# greenhousectrl-lab.net
KiCad netlist of a schematic drawn in EAGLE
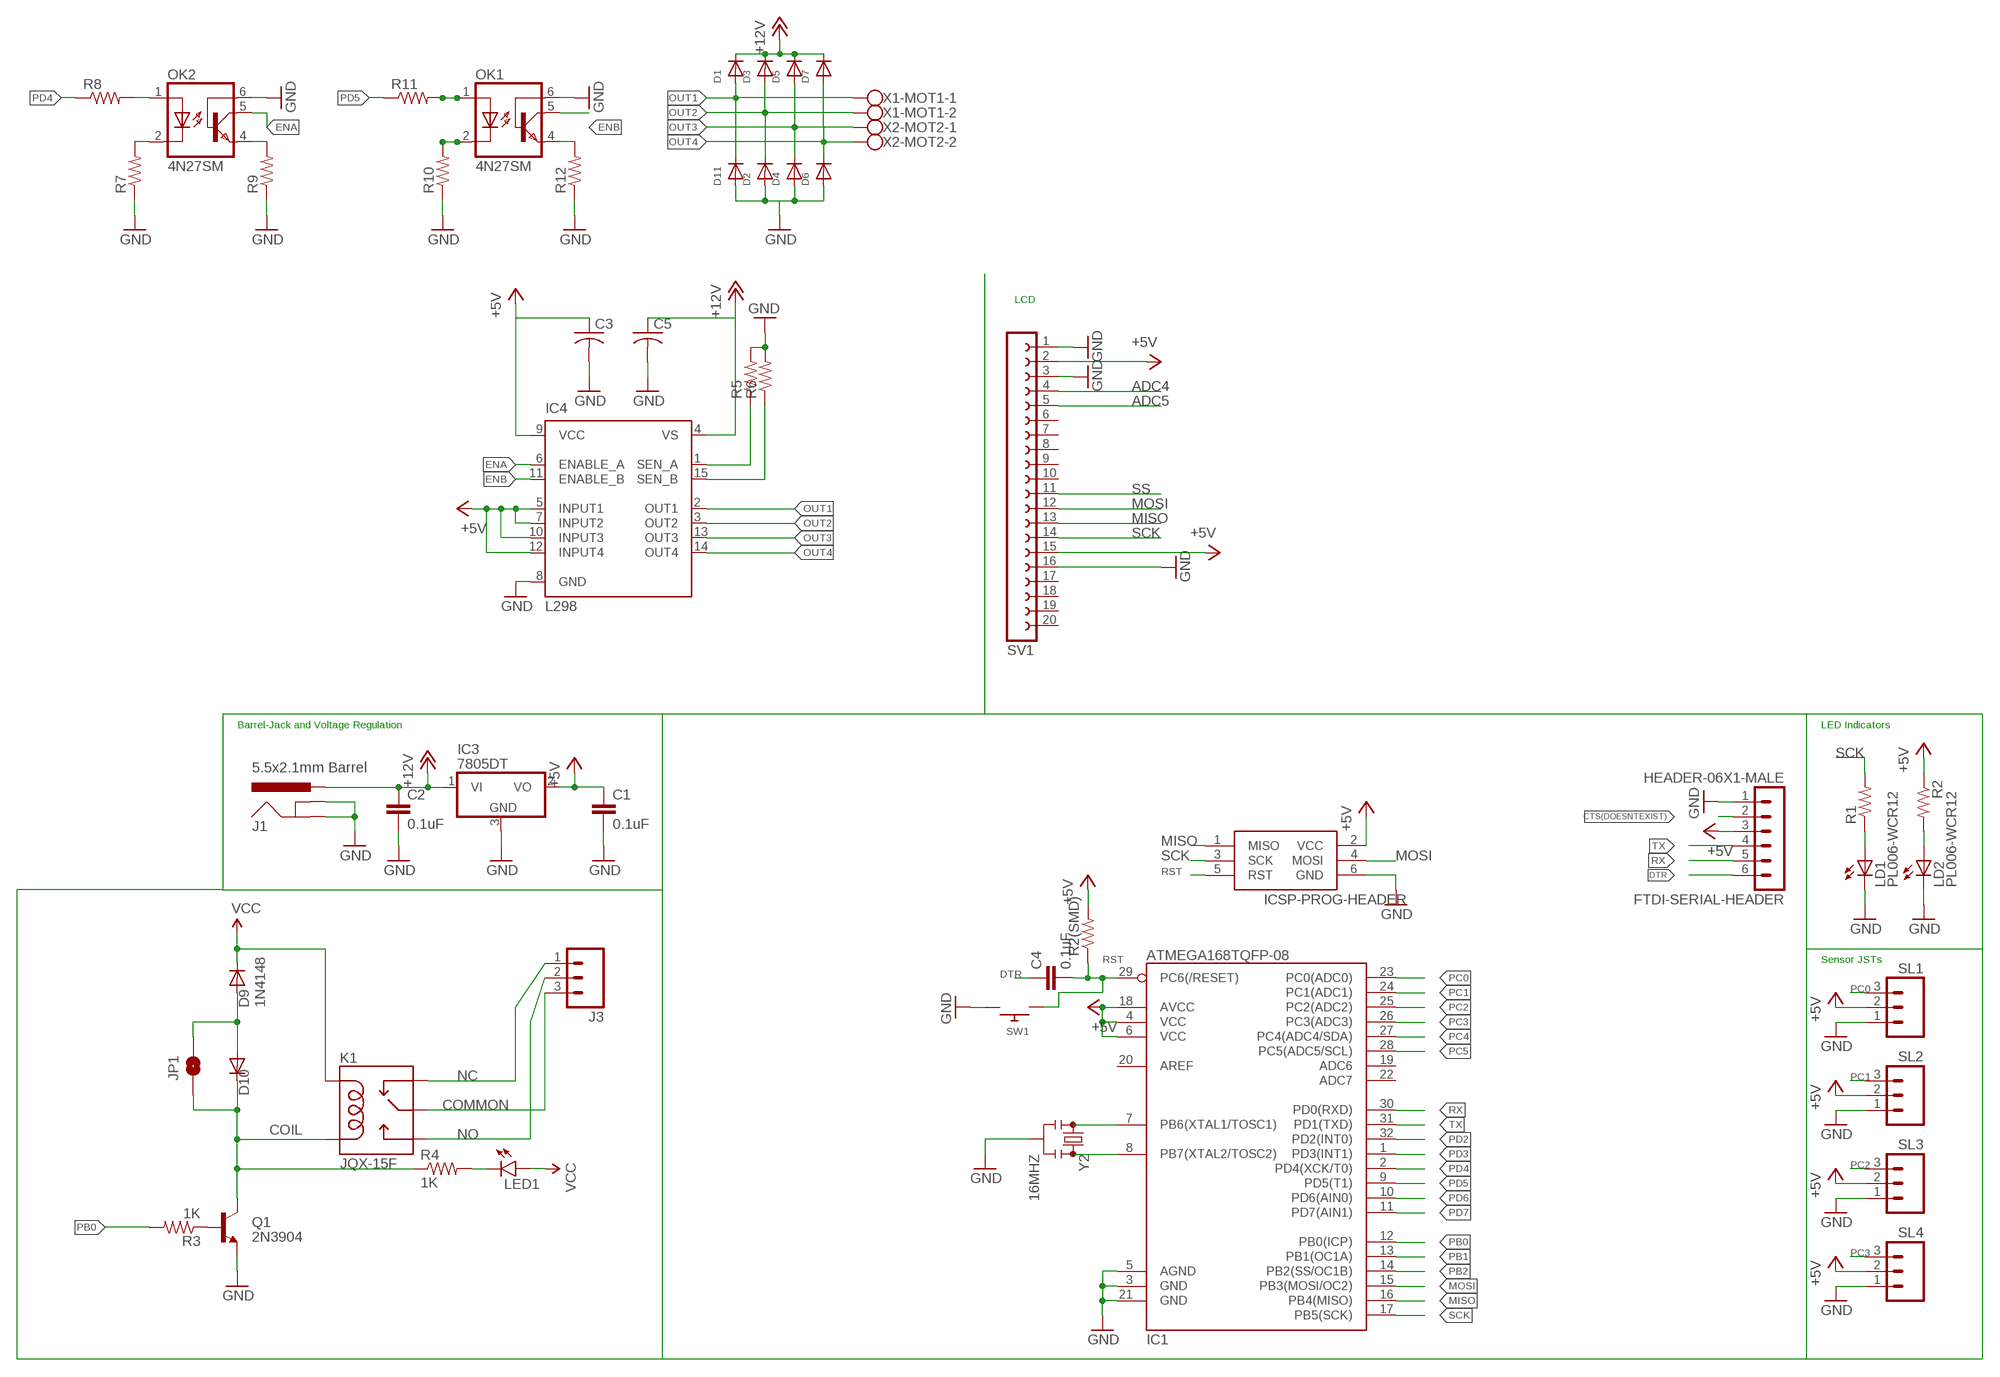
[diagram p0: schematic, sheet 1]

(export (version "E")
  (design (tool "Eeschema 10.0.6"))
  (components
    (comp (ref "C1")
      (value "0.1uF")
      (footprint "eagle-import:0603-CAP")
      (libsource (lib "eagle-import") (part "0.1UF-25V(+80/-20%)(0603)"))
    )
    (comp (ref "C2")
      (value "0.1uF")
      (footprint "eagle-import:0603-CAP")
      (libsource (lib "eagle-import") (part "0.1UF-25V(+80/-20%)(0603)"))
    )
    (comp (ref "C3")
      (value "C-US025-024X044")
      (footprint "eagle-import:C025-024X044")
      (libsource (lib "eagle-import") (part "C-US025-024X044"))
    )
    (comp (ref "C4")
      (value "0.1uF")
      (footprint "eagle-import:0603-CAP")
      (libsource (lib "eagle-import") (part "0.1UF-25V(+80/-20%)(0603)"))
    )
    (comp (ref "C5")
      (value "C-US025-024X044")
      (footprint "eagle-import:C025-024X044")
      (libsource (lib "eagle-import") (part "C-US025-024X044"))
    )
    (comp (ref "D1")
      (value "DIODESMA")
      (footprint "eagle-import:SMADIODE")
      (libsource (lib "eagle-import") (part "DIODESMA"))
    )
    (comp (ref "D2")
      (value "DIODESMA")
      (footprint "eagle-import:SMADIODE")
      (libsource (lib "eagle-import") (part "DIODESMA"))
    )
    (comp (ref "D3")
      (value "DIODESMA")
      (footprint "eagle-import:SMADIODE")
      (libsource (lib "eagle-import") (part "DIODESMA"))
    )
    (comp (ref "D4")
      (value "DIODESMA")
      (footprint "eagle-import:SMADIODE")
      (libsource (lib "eagle-import") (part "DIODESMA"))
    )
    (comp (ref "D5")
      (value "DIODESMA")
      (footprint "eagle-import:SMADIODE")
      (libsource (lib "eagle-import") (part "DIODESMA"))
    )
    (comp (ref "D6")
      (value "DIODESMA")
      (footprint "eagle-import:SMADIODE")
      (libsource (lib "eagle-import") (part "DIODESMA"))
    )
    (comp (ref "D7")
      (value "DIODESMA")
      (footprint "eagle-import:SMADIODE")
      (libsource (lib "eagle-import") (part "DIODESMA"))
    )
    (comp (ref "D9")
      (value "1N4148")
      (footprint "eagle-import:SOD-323F")
      (libsource (lib "eagle-import") (part "DIODESOD-323F"))
    )
    (comp (ref "D10")
      (value "Zener")
      (footprint "eagle-import:SOD-323F")
      (libsource (lib "eagle-import") (part "DIODESOD-323F"))
    )
    (comp (ref "D11")
      (value "DIODESMA")
      (footprint "eagle-import:SMADIODE")
      (libsource (lib "eagle-import") (part "DIODESMA"))
    )
    (comp (ref "FTDI-SERIAL-HEADER")
      (value "HEADER-06X1-MALE")
      (footprint "eagle-import:06X1-PTH")
      (libsource (lib "eagle-import") (part "HEADER-06X1?-MALE"))
    )
    (comp (ref "IC1")
      (value "ATMEGA168TQFP-08")
      (footprint "eagle-import:TQFP32-08")
      (libsource (lib "eagle-import") (part "ATMEGA168TQFP-08"))
    )
    (comp (ref "IC3")
      (value "7805DT")
      (footprint "eagle-import:TO252")
      (libsource (lib "eagle-import") (part "78DT05"))
    )
    (comp (ref "IC4")
      (value "L298")
      (footprint "eagle-import:MULTIWATT-15")
      (fields (field (name "MPN") "L298N"))
      (libsource (lib "eagle-import") (part "L298"))
    )
    (comp (ref "ICSP-PROG-HEADER")
      (value "AVRISP-6")
      (footprint "eagle-import:AVRISP")
      (libsource (lib "eagle-import") (part "AVRISP-6"))
    )
    (comp (ref "J1")
      (value "5.5x2.1mm Barrel")
      (footprint "eagle-import:POWER_JACK_SMD")
      (libsource (lib "eagle-import") (part "POWER_JACKSMD"))
    )
    (comp (ref "J3")
      (value "M03-SCREW-5MM")
      (footprint "eagle-import:SCREWTERMINAL-5MM-3")
      (libsource (lib "eagle-import") (part "M03-SCREW-5MM"))
    )
    (comp (ref "JP1")
      (value "JUMPER-PAD-2-NOYES_SILK")
      (footprint "eagle-import:PAD-JUMPER-2-NO_YES_SILK")
      (libsource (lib "eagle-import") (part "JUMPER-PAD-2-NOYES_SILK"))
    )
    (comp (ref "K1")
      (value "JQX-15F")
      (footprint "eagle-import:RELAY-T90")
      (libsource (lib "eagle-import") (part "RELAYPTH5"))
    )
    (comp (ref "LD1")
      (value "PL006-WCR12")
      (footprint "eagle-import:SOT23")
      (libsource (lib "eagle-import") (part "PL006-WCR12"))
    )
    (comp (ref "LD2")
      (value "PL006-WCR12")
      (footprint "eagle-import:SOT23")
      (libsource (lib "eagle-import") (part "PL006-WCR12"))
    )
    (comp (ref "LED1")
      (value "LED5MM-KIT")
      (footprint "eagle-import:LED5MM-KIT")
      (fields (field (name "PROD_ID") "DIO-09529"))
      (libsource (lib "eagle-import") (part "LED5MM-KIT"))
    )
    (comp (ref "OK1")
      (value "4N27SM")
      (footprint "eagle-import:DIL6-SMD")
      (fields (field (name "MF") "FAIRCHILD SEMICONDUCTOR") (field (name "MPN") "4N27S-M"))
      (libsource (lib "eagle-import") (part "4N?MS27"))
    )
    (comp (ref "OK2")
      (value "4N27SM")
      (footprint "eagle-import:DIL6-SMD")
      (fields (field (name "MF") "FAIRCHILD SEMICONDUCTOR") (field (name "MPN") "4N27S-M"))
      (libsource (lib "eagle-import") (part "4N?MS27"))
    )
    (comp (ref "Q1")
      (value "2N3904")
      (footprint "eagle-import:TO-92-EZ")
      (libsource (lib "eagle-import") (part "TRANSISTOR_NPN2N3904-EZ"))
    )
    (comp (ref "R1")
      (value "R-US_M0805")
      (footprint "eagle-import:M0805")
      (libsource (lib "eagle-import") (part "R-US_M0805"))
    )
    (comp (ref "R2")
      (value "R-US_M0805")
      (footprint "eagle-import:M0805")
      (libsource (lib "eagle-import") (part "R-US_M0805"))
    )
    (comp (ref "R2(SMD)")
      (value "R-US_M0805")
      (footprint "eagle-import:M0805")
      (libsource (lib "eagle-import") (part "R-US_M0805"))
    )
    (comp (ref "R3")
      (value "1K")
      (footprint "eagle-import:M0805")
      (libsource (lib "eagle-import") (part "R-US_M0805"))
    )
    (comp (ref "R4")
      (value "1K")
      (footprint "eagle-import:M0805")
      (libsource (lib "eagle-import") (part "R-US_M0805"))
    )
    (comp (ref "R5")
      (value "R-US_M0805")
      (footprint "eagle-import:M0805")
      (libsource (lib "eagle-import") (part "R-US_M0805"))
    )
    (comp (ref "R6")
      (value "R-US_M0805")
      (footprint "eagle-import:M0805")
      (libsource (lib "eagle-import") (part "R-US_M0805"))
    )
    (comp (ref "R7")
      (value "R-US_M0805")
      (footprint "eagle-import:M0805")
      (libsource (lib "eagle-import") (part "R-US_M0805"))
    )
    (comp (ref "R8")
      (value "R-US_M0805")
      (footprint "eagle-import:M0805")
      (libsource (lib "eagle-import") (part "R-US_M0805"))
    )
    (comp (ref "R9")
      (value "R-US_M0805")
      (footprint "eagle-import:M0805")
      (libsource (lib "eagle-import") (part "R-US_M0805"))
    )
    (comp (ref "R10")
      (value "R-US_M0805")
      (footprint "eagle-import:M0805")
      (libsource (lib "eagle-import") (part "R-US_M0805"))
    )
    (comp (ref "R11")
      (value "R-US_M0805")
      (footprint "eagle-import:M0805")
      (libsource (lib "eagle-import") (part "R-US_M0805"))
    )
    (comp (ref "R12")
      (value "R-US_M0805")
      (footprint "eagle-import:M0805")
      (libsource (lib "eagle-import") (part "R-US_M0805"))
    )
    (comp (ref "SL1")
      (value "M03")
      (footprint "eagle-import:03P")
      (libsource (lib "eagle-import") (part "M03"))
    )
    (comp (ref "SL2")
      (value "M03")
      (footprint "eagle-import:03P")
      (libsource (lib "eagle-import") (part "M03"))
    )
    (comp (ref "SL3")
      (value "M03")
      (footprint "eagle-import:03P")
      (libsource (lib "eagle-import") (part "M03"))
    )
    (comp (ref "SL4")
      (value "M03")
      (footprint "eagle-import:03P")
      (libsource (lib "eagle-import") (part "M03"))
    )
    (comp (ref "SV1")
      (value "FE20-1")
      (footprint "eagle-import:FE20")
      (libsource (lib "eagle-import") (part "FE20-1"))
    )
    (comp (ref "SW1")
      (value "SWITCH_PUSHBUTTONC&K_KSS")
      (footprint "eagle-import:BTN_CK_KSS")
      (libsource (lib "eagle-import") (part "SWITCH_PUSHBUTTONC&K_KSS"))
    )
    (comp (ref "X1-MOT1")
      (value "W237-102")
      (footprint "eagle-import:W237-102")
      (fields (field (name "MPN") "237-102"))
      (libsource (lib "eagle-import") (part "W237-102"))
    )
    (comp (ref "X2-MOT2")
      (value "W237-102")
      (footprint "eagle-import:W237-102")
      (fields (field (name "MPN") "237-102"))
      (libsource (lib "eagle-import") (part "W237-102"))
    )
    (comp (ref "Y2")
      (value "16MHZ")
      (footprint "eagle-import:RESONATOR-SMD")
      (libsource (lib "eagle-import") (part "RESONATOR16MHZ"))
    )
  )
  (nets
    (net (code "1") (name "+5V") (class "Default")
      (node (ref "C1") (pin "1") (pinfunction "1_1") (pintype "passive"))
      (node (ref "C3") (pin "1") (pinfunction "1_1") (pintype "passive"))
      (node (ref "FTDI-SERIAL-HEADER") (pin "3") (pinfunction "3_3") (pintype "passive"))
      (node (ref "IC1") (pin "18") (pinfunction "AVCC_18") (pintype "bidirectional"))
      (node (ref "IC1") (pin "4") (pinfunction "VCC_4") (pintype "bidirectional"))
      (node (ref "IC1") (pin "6") (pinfunction "VCC_6") (pintype "bidirectional"))
      (node (ref "IC3") (pin "2") (pinfunction "VO_2") (pintype "passive"))
      (node (ref "IC4") (pin "10") (pinfunction "INPUT3_10") (pintype "input"))
      (node (ref "IC4") (pin "12") (pinfunction "INPUT4_12") (pintype "input"))
      (node (ref "IC4") (pin "5") (pinfunction "INPUT1_5") (pintype "input"))
      (node (ref "IC4") (pin "7") (pinfunction "INPUT2_7") (pintype "input"))
      (node (ref "IC4") (pin "9") (pinfunction "VCC_9") (pintype "power_in"))
      (node (ref "ICSP-PROG-HEADER") (pin "2") (pinfunction "VCC_2") (pintype "power_in"))
      (node (ref "R2") (pin "1") (pinfunction "1_1") (pintype "passive"))
      (node (ref "R2(SMD)") (pin "2") (pinfunction "2_2") (pintype "passive"))
      (node (ref "SL1") (pin "2") (pinfunction "2_2") (pintype "passive"))
      (node (ref "SL2") (pin "2") (pinfunction "2_2") (pintype "passive"))
      (node (ref "SL3") (pin "2") (pinfunction "2_2") (pintype "passive"))
      (node (ref "SL4") (pin "2") (pinfunction "2_2") (pintype "passive"))
      (node (ref "SV1") (pin "15") (pinfunction "15_15") (pintype "passive"))
      (node (ref "SV1") (pin "2") (pinfunction "2_2") (pintype "passive"))
    )
    (net (code "2") (name "+12V") (class "Default")
      (node (ref "C2") (pin "1") (pinfunction "1_1") (pintype "passive"))
      (node (ref "C5") (pin "1") (pinfunction "1_1") (pintype "passive"))
      (node (ref "D1") (pin "C") (pinfunction "C_C") (pintype "passive"))
      (node (ref "D3") (pin "C") (pinfunction "C_C") (pintype "passive"))
      (node (ref "D5") (pin "C") (pinfunction "C_C") (pintype "passive"))
      (node (ref "D7") (pin "C") (pinfunction "C_C") (pintype "passive"))
      (node (ref "IC3") (pin "1") (pinfunction "VI_1") (pintype "input"))
      (node (ref "IC4") (pin "4") (pinfunction "VS_4") (pintype "power_in"))
      (node (ref "J1") (pin "VIN0") (pinfunction "PWR_VIN0") (pintype "bidirectional"))
    )
    (net (code "3") (name "/ADC4") (class "Default")
      (node (ref "SV1") (pin "4") (pinfunction "4_4") (pintype "passive"))
    )
    (net (code "4") (name "/ADC5") (class "Default")
      (node (ref "SV1") (pin "5") (pinfunction "5_5") (pintype "passive"))
    )
    (net (code "5") (name "/COIL") (class "Default")
      (node (ref "D10") (pin "C") (pinfunction "C_C") (pintype "passive"))
      (node (ref "JP1") (pin "1") (pinfunction "1_1") (pintype "passive"))
      (node (ref "K1") (pin "COIL2") (pinfunction "COIL2_COIL2") (pintype "bidirectional"))
      (node (ref "Q1") (pin "3") (pinfunction "C_3") (pintype "passive"))
      (node (ref "R4") (pin "1") (pinfunction "1_1") (pintype "passive"))
    )
    (net (code "6") (name "/COMMON") (class "Default")
      (node (ref "J3") (pin "3") (pinfunction "3_3") (pintype "passive"))
      (node (ref "K1") (pin "MAIN") (pinfunction "MAIN_MAIN") (pintype "bidirectional"))
    )
    (net (code "7") (name "/NC") (class "Default")
      (node (ref "J3") (pin "1") (pinfunction "1_1") (pintype "passive"))
      (node (ref "K1") (pin "NC") (pinfunction "NC_NC") (pintype "bidirectional"))
    )
    (net (code "8") (name "/NO") (class "Default")
      (node (ref "J3") (pin "2") (pinfunction "2_2") (pintype "passive"))
      (node (ref "K1") (pin "NO") (pinfunction "NO_NO") (pintype "bidirectional"))
    )
    (net (code "9") (name "/RST") (class "Default")
      (node (ref "C4") (pin "2") (pinfunction "2_2") (pintype "passive"))
      (node (ref "IC1") (pin "29") (pinfunction "PC6(/RESET)_29") (pintype "bidirectional"))
      (node (ref "ICSP-PROG-HEADER") (pin "5") (pinfunction "RST_5") (pintype "output"))
      (node (ref "R2(SMD)") (pin "1") (pinfunction "1_1") (pintype "passive"))
      (node (ref "SW1") (pin "P$1") (pinfunction "P$1_P$1") (pintype "passive"))
    )
    (net (code "10") (name "/SS") (class "Default")
      (node (ref "SV1") (pin "11") (pinfunction "11_11") (pintype "passive"))
    )
    (net (code "11") (name "CTS(DOESNTEXIST)") (class "Default")
      (node (ref "FTDI-SERIAL-HEADER") (pin "2") (pinfunction "2_2") (pintype "passive"))
    )
    (net (code "12") (name "DTR") (class "Default")
      (node (ref "C4") (pin "1") (pinfunction "1_1") (pintype "passive"))
      (node (ref "FTDI-SERIAL-HEADER") (pin "6") (pinfunction "6_6") (pintype "passive"))
    )
    (net (code "13") (name "ENA") (class "Default")
      (node (ref "IC4") (pin "6") (pinfunction "ENABLE_A_6") (pintype "input"))
      (node (ref "OK2") (pin "5") (pinfunction "COL_5") (pintype "passive"))
    )
    (net (code "14") (name "ENB") (class "Default")
      (node (ref "IC4") (pin "11") (pinfunction "ENABLE_B_11") (pintype "input"))
      (node (ref "OK1") (pin "5") (pinfunction "COL_5") (pintype "passive"))
    )
    (net (code "15") (name "GND") (class "Default")
      (node (ref "C1") (pin "2") (pinfunction "2_2") (pintype "passive"))
      (node (ref "C2") (pin "2") (pinfunction "2_2") (pintype "passive"))
      (node (ref "C3") (pin "2") (pinfunction "2_2") (pintype "passive"))
      (node (ref "C5") (pin "2") (pinfunction "2_2") (pintype "passive"))
      (node (ref "D11") (pin "A") (pinfunction "A_A") (pintype "passive"))
      (node (ref "D2") (pin "A") (pinfunction "A_A") (pintype "passive"))
      (node (ref "D4") (pin "A") (pinfunction "A_A") (pintype "passive"))
      (node (ref "D6") (pin "A") (pinfunction "A_A") (pintype "passive"))
      (node (ref "FTDI-SERIAL-HEADER") (pin "1") (pinfunction "1_1") (pintype "passive"))
      (node (ref "IC1") (pin "21") (pinfunction "GND_21") (pintype "bidirectional"))
      (node (ref "IC1") (pin "3") (pinfunction "GND_3") (pintype "bidirectional"))
      (node (ref "IC1") (pin "5") (pinfunction "AGND_5") (pintype "bidirectional"))
      (node (ref "IC3") (pin "3") (pinfunction "GND_3") (pintype "passive"))
      (node (ref "IC4") (pin "8") (pinfunction "GND_8") (pintype "power_in"))
      (node (ref "ICSP-PROG-HEADER") (pin "6") (pinfunction "GND_6") (pintype "power_in"))
      (node (ref "J1") (pin "GND") (pinfunction "GNDBREAK_GND") (pintype "bidirectional"))
      (node (ref "J1") (pin "P$4") (pinfunction "GND_P$4") (pintype "bidirectional"))
      (node (ref "LD1") (pin "3") (pinfunction "C_3") (pintype "passive"))
      (node (ref "LD2") (pin "3") (pinfunction "C_3") (pintype "passive"))
      (node (ref "OK1") (pin "6") (pinfunction "BAS_6") (pintype "passive"))
      (node (ref "OK2") (pin "6") (pinfunction "BAS_6") (pintype "passive"))
      (node (ref "Q1") (pin "1") (pinfunction "E_1") (pintype "passive"))
      (node (ref "R10") (pin "1") (pinfunction "1_1") (pintype "passive"))
      (node (ref "R12") (pin "1") (pinfunction "1_1") (pintype "passive"))
      (node (ref "R5") (pin "2") (pinfunction "2_2") (pintype "passive"))
      (node (ref "R6") (pin "2") (pinfunction "2_2") (pintype "passive"))
      (node (ref "R7") (pin "1") (pinfunction "1_1") (pintype "passive"))
      (node (ref "R9") (pin "1") (pinfunction "1_1") (pintype "passive"))
      (node (ref "SL1") (pin "1") (pinfunction "1_1") (pintype "passive"))
      (node (ref "SL2") (pin "1") (pinfunction "1_1") (pintype "passive"))
      (node (ref "SL3") (pin "1") (pinfunction "1_1") (pintype "passive"))
      (node (ref "SL4") (pin "1") (pinfunction "1_1") (pintype "passive"))
      (node (ref "SV1") (pin "1") (pinfunction "1_1") (pintype "passive"))
      (node (ref "SV1") (pin "16") (pinfunction "16_16") (pintype "passive"))
      (node (ref "SV1") (pin "3") (pinfunction "3_3") (pintype "passive"))
      (node (ref "SW1") (pin "P$2") (pinfunction "P$2_P$2") (pintype "passive"))
      (node (ref "Y2") (pin "2") (pinfunction "2_2") (pintype "passive"))
    )
    (net (code "16") (name "MISO") (class "Default")
      (node (ref "IC1") (pin "16") (pinfunction "PB4(MISO)_16") (pintype "bidirectional"))
      (node (ref "ICSP-PROG-HEADER") (pin "1") (pinfunction "MISO_1") (pintype "input"))
      (node (ref "SV1") (pin "13") (pinfunction "13_13") (pintype "passive"))
    )
    (net (code "17") (name "MOSI") (class "Default")
      (node (ref "IC1") (pin "15") (pinfunction "PB3(MOSI/OC2)_15") (pintype "bidirectional"))
      (node (ref "ICSP-PROG-HEADER") (pin "4") (pinfunction "MOSI_4") (pintype "output"))
      (node (ref "SV1") (pin "12") (pinfunction "12_12") (pintype "passive"))
    )
    (net (code "18") (name "Net-(D10-PadA)") (class "Default")
      (node (ref "D10") (pin "A") (pinfunction "A_A") (pintype "passive"))
      (node (ref "D9") (pin "A") (pinfunction "A_A") (pintype "passive"))
      (node (ref "JP1") (pin "2") (pinfunction "2_2") (pintype "passive"))
    )
    (net (code "19") (name "Net-(IC1-PB6(XTAL1{slash}TOSC1))") (class "Default")
      (node (ref "IC1") (pin "7") (pinfunction "PB6(XTAL1/TOSC1)_7") (pintype "bidirectional"))
      (node (ref "Y2") (pin "1") (pinfunction "1_1") (pintype "passive"))
    )
    (net (code "20") (name "Net-(IC1-PB7(XTAL2{slash}TOSC2))") (class "Default")
      (node (ref "IC1") (pin "8") (pinfunction "PB7(XTAL2/TOSC2)_8") (pintype "bidirectional"))
      (node (ref "Y2") (pin "3") (pinfunction "3_3") (pintype "passive"))
    )
    (net (code "21") (name "Net-(IC4-SEN_A)") (class "Default")
      (node (ref "IC4") (pin "1") (pinfunction "SEN_A_1") (pintype "input"))
      (node (ref "R5") (pin "1") (pinfunction "1_1") (pintype "passive"))
    )
    (net (code "22") (name "Net-(IC4-SEN_B)") (class "Default")
      (node (ref "IC4") (pin "15") (pinfunction "SEN_B_15") (pintype "input"))
      (node (ref "R6") (pin "1") (pinfunction "1_1") (pintype "passive"))
    )
    (net (code "23") (name "Net-(LD1-A)") (class "Default")
      (node (ref "LD1") (pin "1") (pinfunction "A_1") (pintype "passive"))
      (node (ref "R1") (pin "1") (pinfunction "1_1") (pintype "passive"))
    )
    (net (code "24") (name "Net-(LD2-A)") (class "Default")
      (node (ref "LD2") (pin "1") (pinfunction "A_1") (pintype "passive"))
      (node (ref "R2") (pin "2") (pinfunction "2_2") (pintype "passive"))
    )
    (net (code "25") (name "Net-(LED1-C)") (class "Default")
      (node (ref "LED1") (pin "K") (pinfunction "C_K") (pintype "passive"))
      (node (ref "R4") (pin "2") (pinfunction "2_2") (pintype "passive"))
    )
    (net (code "26") (name "Net-(OK1-A)") (class "Default")
      (node (ref "OK1") (pin "1") (pinfunction "A_1") (pintype "passive"))
      (node (ref "R11") (pin "2") (pinfunction "2_2") (pintype "passive"))
    )
    (net (code "27") (name "Net-(OK1-C)") (class "Default")
      (node (ref "OK1") (pin "2") (pinfunction "C_2") (pintype "passive"))
      (node (ref "R10") (pin "2") (pinfunction "2_2") (pintype "passive"))
    )
    (net (code "28") (name "Net-(OK1-EMI)") (class "Default")
      (node (ref "OK1") (pin "4") (pinfunction "EMI_4") (pintype "passive"))
      (node (ref "R12") (pin "2") (pinfunction "2_2") (pintype "passive"))
    )
    (net (code "29") (name "Net-(OK2-A)") (class "Default")
      (node (ref "OK2") (pin "1") (pinfunction "A_1") (pintype "passive"))
      (node (ref "R8") (pin "2") (pinfunction "2_2") (pintype "passive"))
    )
    (net (code "30") (name "Net-(OK2-C)") (class "Default")
      (node (ref "OK2") (pin "2") (pinfunction "C_2") (pintype "passive"))
      (node (ref "R7") (pin "2") (pinfunction "2_2") (pintype "passive"))
    )
    (net (code "31") (name "Net-(OK2-EMI)") (class "Default")
      (node (ref "OK2") (pin "4") (pinfunction "EMI_4") (pintype "passive"))
      (node (ref "R9") (pin "2") (pinfunction "2_2") (pintype "passive"))
    )
    (net (code "32") (name "Net-(Q1-B)") (class "Default")
      (node (ref "Q1") (pin "2") (pinfunction "B_2") (pintype "passive"))
      (node (ref "R3") (pin "1") (pinfunction "1_1") (pintype "passive"))
    )
    (net (code "33") (name "OUT1") (class "Default")
      (node (ref "D1") (pin "A") (pinfunction "A_A") (pintype "passive"))
      (node (ref "D11") (pin "C") (pinfunction "C_C") (pintype "passive"))
      (node (ref "IC4") (pin "2") (pinfunction "OUT1_2") (pintype "output"))
      (node (ref "X1-MOT1") (pin "1") (pinfunction "KL_1") (pintype "passive"))
    )
    (net (code "34") (name "OUT2") (class "Default")
      (node (ref "D2") (pin "C") (pinfunction "C_C") (pintype "passive"))
      (node (ref "D3") (pin "A") (pinfunction "A_A") (pintype "passive"))
      (node (ref "IC4") (pin "3") (pinfunction "OUT2_3") (pintype "output"))
      (node (ref "X1-MOT1") (pin "2") (pinfunction "KL_2") (pintype "passive"))
    )
    (net (code "35") (name "OUT3") (class "Default")
      (node (ref "D4") (pin "C") (pinfunction "C_C") (pintype "passive"))
      (node (ref "D5") (pin "A") (pinfunction "A_A") (pintype "passive"))
      (node (ref "IC4") (pin "13") (pinfunction "OUT3_13") (pintype "output"))
      (node (ref "X2-MOT2") (pin "1") (pinfunction "KL_1") (pintype "passive"))
    )
    (net (code "36") (name "OUT4") (class "Default")
      (node (ref "D6") (pin "C") (pinfunction "C_C") (pintype "passive"))
      (node (ref "D7") (pin "A") (pinfunction "A_A") (pintype "passive"))
      (node (ref "IC4") (pin "14") (pinfunction "OUT4_14") (pintype "output"))
      (node (ref "X2-MOT2") (pin "2") (pinfunction "KL_2") (pintype "passive"))
    )
    (net (code "37") (name "PB0") (class "Default")
      (node (ref "IC1") (pin "12") (pinfunction "PB0(ICP)_12") (pintype "bidirectional"))
      (node (ref "R3") (pin "2") (pinfunction "2_2") (pintype "passive"))
    )
    (net (code "38") (name "PB1") (class "Default")
      (node (ref "IC1") (pin "13") (pinfunction "PB1(OC1A)_13") (pintype "bidirectional"))
    )
    (net (code "39") (name "PB2") (class "Default")
      (node (ref "IC1") (pin "14") (pinfunction "PB2(SS/OC1B)_14") (pintype "bidirectional"))
    )
    (net (code "40") (name "PC0") (class "Default")
      (node (ref "IC1") (pin "23") (pinfunction "PC0(ADC0)_23") (pintype "bidirectional"))
      (node (ref "SL1") (pin "3") (pinfunction "3_3") (pintype "passive"))
    )
    (net (code "41") (name "PC1") (class "Default")
      (node (ref "IC1") (pin "24") (pinfunction "PC1(ADC1)_24") (pintype "bidirectional"))
      (node (ref "SL2") (pin "3") (pinfunction "3_3") (pintype "passive"))
    )
    (net (code "42") (name "PC2") (class "Default")
      (node (ref "IC1") (pin "25") (pinfunction "PC2(ADC2)_25") (pintype "bidirectional"))
      (node (ref "SL3") (pin "3") (pinfunction "3_3") (pintype "passive"))
    )
    (net (code "43") (name "PC3") (class "Default")
      (node (ref "IC1") (pin "26") (pinfunction "PC3(ADC3)_26") (pintype "bidirectional"))
      (node (ref "SL4") (pin "3") (pinfunction "3_3") (pintype "passive"))
    )
    (net (code "44") (name "PC4") (class "Default")
      (node (ref "IC1") (pin "27") (pinfunction "PC4(ADC4/SDA)_27") (pintype "bidirectional"))
    )
    (net (code "45") (name "PC5") (class "Default")
      (node (ref "IC1") (pin "28") (pinfunction "PC5(ADC5/SCL)_28") (pintype "bidirectional"))
    )
    (net (code "46") (name "PD2") (class "Default")
      (node (ref "IC1") (pin "32") (pinfunction "PD2(INT0)_32") (pintype "bidirectional"))
    )
    (net (code "47") (name "PD3") (class "Default")
      (node (ref "IC1") (pin "1") (pinfunction "PD3(INT1)_1") (pintype "bidirectional"))
    )
    (net (code "48") (name "PD4") (class "Default")
      (node (ref "IC1") (pin "2") (pinfunction "PD4(XCK/T0)_2") (pintype "bidirectional"))
      (node (ref "R8") (pin "1") (pinfunction "1_1") (pintype "passive"))
    )
    (net (code "49") (name "PD5") (class "Default")
      (node (ref "IC1") (pin "9") (pinfunction "PD5(T1)_9") (pintype "bidirectional"))
      (node (ref "R11") (pin "1") (pinfunction "1_1") (pintype "passive"))
    )
    (net (code "50") (name "PD6") (class "Default")
      (node (ref "IC1") (pin "10") (pinfunction "PD6(AIN0)_10") (pintype "bidirectional"))
    )
    (net (code "51") (name "PD7") (class "Default")
      (node (ref "IC1") (pin "11") (pinfunction "PD7(AIN1)_11") (pintype "bidirectional"))
    )
    (net (code "52") (name "RX") (class "Default")
      (node (ref "FTDI-SERIAL-HEADER") (pin "5") (pinfunction "5_5") (pintype "passive"))
      (node (ref "IC1") (pin "30") (pinfunction "PD0(RXD)_30") (pintype "bidirectional"))
    )
    (net (code "53") (name "SCK") (class "Default")
      (node (ref "IC1") (pin "17") (pinfunction "PB5(SCK)_17") (pintype "bidirectional"))
      (node (ref "ICSP-PROG-HEADER") (pin "3") (pinfunction "SCK_3") (pintype "output"))
      (node (ref "R1") (pin "2") (pinfunction "2_2") (pintype "passive"))
      (node (ref "SV1") (pin "14") (pinfunction "14_14") (pintype "passive"))
    )
    (net (code "54") (name "TX") (class "Default")
      (node (ref "FTDI-SERIAL-HEADER") (pin "4") (pinfunction "4_4") (pintype "passive"))
      (node (ref "IC1") (pin "31") (pinfunction "PD1(TXD)_31") (pintype "bidirectional"))
    )
    (net (code "55") (name "VCC") (class "Default")
      (node (ref "D9") (pin "C") (pinfunction "C_C") (pintype "passive"))
      (node (ref "K1") (pin "COIL1") (pinfunction "COIL1_COIL1") (pintype "bidirectional"))
      (node (ref "LED1") (pin "A") (pinfunction "A_A") (pintype "passive"))
    )
    (net (code "56") (name "unconnected-(IC1-ADC6-Pad19)") (class "Default")
      (node (ref "IC1") (pin "19") (pinfunction "ADC6_19") (pintype "bidirectional"))
    )
    (net (code "57") (name "unconnected-(IC1-ADC7-Pad22)") (class "Default")
      (node (ref "IC1") (pin "22") (pinfunction "ADC7_22") (pintype "bidirectional"))
    )
    (net (code "58") (name "unconnected-(IC1-AREF-Pad20)") (class "Default")
      (node (ref "IC1") (pin "20") (pinfunction "AREF_20") (pintype "bidirectional"))
    )
    (net (code "59") (name "unconnected-(SV1-Pad6)") (class "Default")
      (node (ref "SV1") (pin "6") (pinfunction "6_6") (pintype "passive"))
    )
    (net (code "60") (name "unconnected-(SV1-Pad7)") (class "Default")
      (node (ref "SV1") (pin "7") (pinfunction "7_7") (pintype "passive"))
    )
    (net (code "61") (name "unconnected-(SV1-Pad8)") (class "Default")
      (node (ref "SV1") (pin "8") (pinfunction "8_8") (pintype "passive"))
    )
    (net (code "62") (name "unconnected-(SV1-Pad9)") (class "Default")
      (node (ref "SV1") (pin "9") (pinfunction "9_9") (pintype "passive"))
    )
    (net (code "63") (name "unconnected-(SV1-Pad10)") (class "Default")
      (node (ref "SV1") (pin "10") (pinfunction "10_10") (pintype "passive"))
    )
    (net (code "64") (name "unconnected-(SV1-Pad17)") (class "Default")
      (node (ref "SV1") (pin "17") (pinfunction "17_17") (pintype "passive"))
    )
    (net (code "65") (name "unconnected-(SV1-Pad18)") (class "Default")
      (node (ref "SV1") (pin "18") (pinfunction "18_18") (pintype "passive"))
    )
    (net (code "66") (name "unconnected-(SV1-Pad19)") (class "Default")
      (node (ref "SV1") (pin "19") (pinfunction "19_19") (pintype "passive"))
    )
    (net (code "67") (name "unconnected-(SV1-Pad20)") (class "Default")
      (node (ref "SV1") (pin "20") (pinfunction "20_20") (pintype "passive"))
    )
  )
)
